# Sheet1.net
KiCad netlist of a schematic drawn in Altium Designer
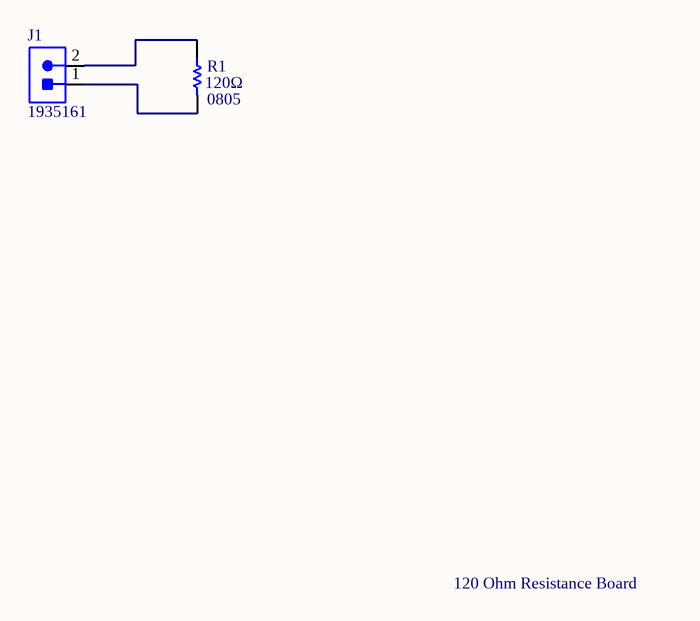
[diagram p0: Sheet1.SchDoc]

(export (version "E")
  (design (tool "Eeschema 10.0.6"))
  (components
    (comp (ref "J1")
      (value "CON_2M_TERM")
      (footprint "1935161")
      (description "TERM BLK 2POS SIDE ENTRY 5MM")
      (fields (field (name "VOLTAGE") "300V") (field (name "MANUFACTURER PART NUMBER 1") "1935161"))
      (libsource (lib "UWRT_Schematic_Library_2020") (part "CON_2M_TERM"))
    )
    (comp (ref "R1")
      (value "RES_120Ω_0805_1%")
      (footprint "RESC0805")
      (description "RES 120 OHM 1% 1/8W 0805")
      (fields
        (field (name "LCSC PART #") "C17437")
        (field (name "PACKAGE/FOOTPRINT") "0805")
        (field (name "RESISTANCE") "120Ω")
      )
      (libsource (lib "UWRT_Schematic_Library_2020") (part "RES_120Ω_0805_1%"))
    )
  )
  (nets
    (net (code "1") (name "Net-(J1-Pad1)") (class "Default")
      (node (ref "J1") (pin "1") (pinfunction "1_1") (pintype "passive"))
      (node (ref "R1") (pin "2") (pinfunction "2_2") (pintype "passive"))
    )
    (net (code "2") (name "Net-(J1-Pad2)") (class "Default")
      (node (ref "J1") (pin "2") (pinfunction "2_2") (pintype "passive"))
      (node (ref "R1") (pin "1") (pinfunction "1_1") (pintype "passive"))
    )
  )
)
